# Esp32IoAdapt.net
KiCad netlist of a schematic drawn in EAGLE
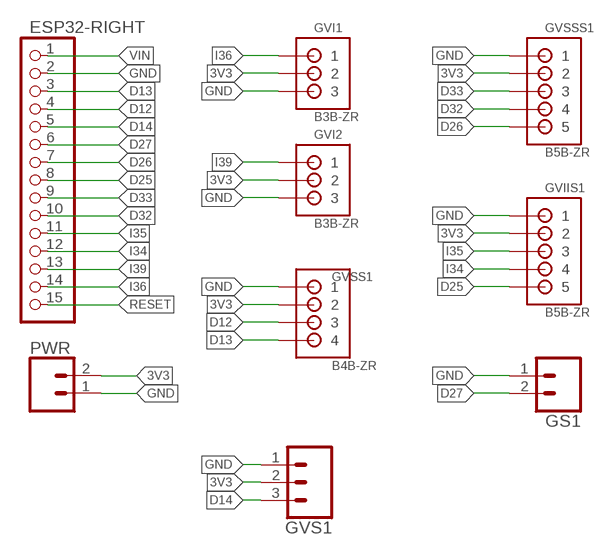
[diagram p0: schematic, sheet 1]

(export (version "E")
  (design (tool "Eeschema 10.0.6"))
  (components
    (comp (ref "ESP32-RIGHT")
      (value "0")
      (footprint "eagle-import:1X15")
      (libsource (lib "eagle-import") (part "PINHD-1X15"))
    )
    (comp (ref "GS1")
      (value "CONN_02")
      (footprint "eagle-import:1X02")
      (libsource (lib "eagle-import") (part "CONN_02"))
    )
    (comp (ref "GVI1")
      (value "B3B-ZR")
      (footprint "eagle-import:B3B-ZR")
      (libsource (lib "eagle-import") (part "B3B-ZR"))
    )
    (comp (ref "GVI2")
      (value "B3B-ZR")
      (footprint "eagle-import:B3B-ZR")
      (libsource (lib "eagle-import") (part "B3B-ZR"))
    )
    (comp (ref "GVIIS1")
      (value "B5B-ZR")
      (footprint "eagle-import:B5B-ZR")
      (libsource (lib "eagle-import") (part "B5B-ZR"))
    )
    (comp (ref "GVS1")
      (value "CONN_03")
      (footprint "eagle-import:1X03")
      (libsource (lib "eagle-import") (part "CONN_03"))
    )
    (comp (ref "GVSS1")
      (value "B4B-ZR")
      (footprint "eagle-import:B4B-ZR")
      (libsource (lib "eagle-import") (part "B4B-ZR"))
    )
    (comp (ref "GVSSS1")
      (value "B5B-ZR")
      (footprint "eagle-import:B5B-ZR")
      (libsource (lib "eagle-import") (part "B5B-ZR"))
    )
    (comp (ref "PWR")
      (value "CONN_02")
      (footprint "eagle-import:1X02")
      (libsource (lib "eagle-import") (part "CONN_02"))
    )
  )
  (nets
    (net (code "1") (name "3V3") (class "Default")
      (node (ref "GVI1") (pin "2") (pinfunction "2_2") (pintype "bidirectional"))
      (node (ref "GVI2") (pin "2") (pinfunction "2_2") (pintype "bidirectional"))
      (node (ref "GVIIS1") (pin "2") (pinfunction "2_2") (pintype "bidirectional"))
      (node (ref "GVS1") (pin "2") (pinfunction "2_2") (pintype "passive"))
      (node (ref "GVSS1") (pin "2") (pinfunction "2_2") (pintype "bidirectional"))
      (node (ref "GVSSS1") (pin "2") (pinfunction "2_2") (pintype "bidirectional"))
      (node (ref "PWR") (pin "2") (pinfunction "2_2") (pintype "passive"))
    )
    (net (code "2") (name "D12") (class "Default")
      (node (ref "ESP32-RIGHT") (pin "4") (pinfunction "4_4") (pintype "passive"))
      (node (ref "GVSS1") (pin "3") (pinfunction "3_3") (pintype "bidirectional"))
    )
    (net (code "3") (name "D13") (class "Default")
      (node (ref "ESP32-RIGHT") (pin "3") (pinfunction "3_3") (pintype "passive"))
      (node (ref "GVSS1") (pin "4") (pinfunction "4_4") (pintype "bidirectional"))
    )
    (net (code "4") (name "D14") (class "Default")
      (node (ref "ESP32-RIGHT") (pin "5") (pinfunction "5_5") (pintype "passive"))
      (node (ref "GVS1") (pin "3") (pinfunction "3_3") (pintype "passive"))
    )
    (net (code "5") (name "D25") (class "Default")
      (node (ref "ESP32-RIGHT") (pin "8") (pinfunction "8_8") (pintype "passive"))
      (node (ref "GVIIS1") (pin "5") (pinfunction "5_5") (pintype "bidirectional"))
    )
    (net (code "6") (name "D26") (class "Default")
      (node (ref "ESP32-RIGHT") (pin "7") (pinfunction "7_7") (pintype "passive"))
      (node (ref "GVSSS1") (pin "5") (pinfunction "5_5") (pintype "bidirectional"))
    )
    (net (code "7") (name "D27") (class "Default")
      (node (ref "ESP32-RIGHT") (pin "6") (pinfunction "6_6") (pintype "passive"))
      (node (ref "GS1") (pin "2") (pinfunction "2_2") (pintype "passive"))
    )
    (net (code "8") (name "D32") (class "Default")
      (node (ref "ESP32-RIGHT") (pin "10") (pinfunction "10_10") (pintype "passive"))
      (node (ref "GVSSS1") (pin "4") (pinfunction "4_4") (pintype "bidirectional"))
    )
    (net (code "9") (name "D33") (class "Default")
      (node (ref "ESP32-RIGHT") (pin "9") (pinfunction "9_9") (pintype "passive"))
      (node (ref "GVSSS1") (pin "3") (pinfunction "3_3") (pintype "bidirectional"))
    )
    (net (code "10") (name "GND") (class "Default")
      (node (ref "ESP32-RIGHT") (pin "2") (pinfunction "2_2") (pintype "passive"))
      (node (ref "GS1") (pin "1") (pinfunction "1_1") (pintype "passive"))
      (node (ref "GVI1") (pin "3") (pinfunction "3_3") (pintype "bidirectional"))
      (node (ref "GVI2") (pin "3") (pinfunction "3_3") (pintype "bidirectional"))
      (node (ref "GVIIS1") (pin "1") (pinfunction "1_1") (pintype "bidirectional"))
      (node (ref "GVS1") (pin "1") (pinfunction "1_1") (pintype "passive"))
      (node (ref "GVSS1") (pin "1") (pinfunction "1_1") (pintype "bidirectional"))
      (node (ref "GVSSS1") (pin "1") (pinfunction "1_1") (pintype "bidirectional"))
      (node (ref "PWR") (pin "1") (pinfunction "1_1") (pintype "passive"))
    )
    (net (code "11") (name "I34") (class "Default")
      (node (ref "ESP32-RIGHT") (pin "12") (pinfunction "12_12") (pintype "passive"))
      (node (ref "GVIIS1") (pin "4") (pinfunction "4_4") (pintype "bidirectional"))
    )
    (net (code "12") (name "I35") (class "Default")
      (node (ref "ESP32-RIGHT") (pin "11") (pinfunction "11_11") (pintype "passive"))
      (node (ref "GVIIS1") (pin "3") (pinfunction "3_3") (pintype "bidirectional"))
    )
    (net (code "13") (name "I36") (class "Default")
      (node (ref "ESP32-RIGHT") (pin "14") (pinfunction "14_14") (pintype "passive"))
      (node (ref "GVI1") (pin "1") (pinfunction "1_1") (pintype "bidirectional"))
    )
    (net (code "14") (name "I39") (class "Default")
      (node (ref "ESP32-RIGHT") (pin "13") (pinfunction "13_13") (pintype "passive"))
      (node (ref "GVI2") (pin "1") (pinfunction "1_1") (pintype "bidirectional"))
    )
    (net (code "15") (name "RESET") (class "Default")
      (node (ref "ESP32-RIGHT") (pin "15") (pinfunction "15_15") (pintype "passive"))
    )
    (net (code "16") (name "VIN") (class "Default")
      (node (ref "ESP32-RIGHT") (pin "1") (pinfunction "1_1") (pintype "passive"))
    )
  )
)
